# ST_SYS_Board_FPGA_SUP.net
KiCad netlist of a schematic drawn in Altium Designer
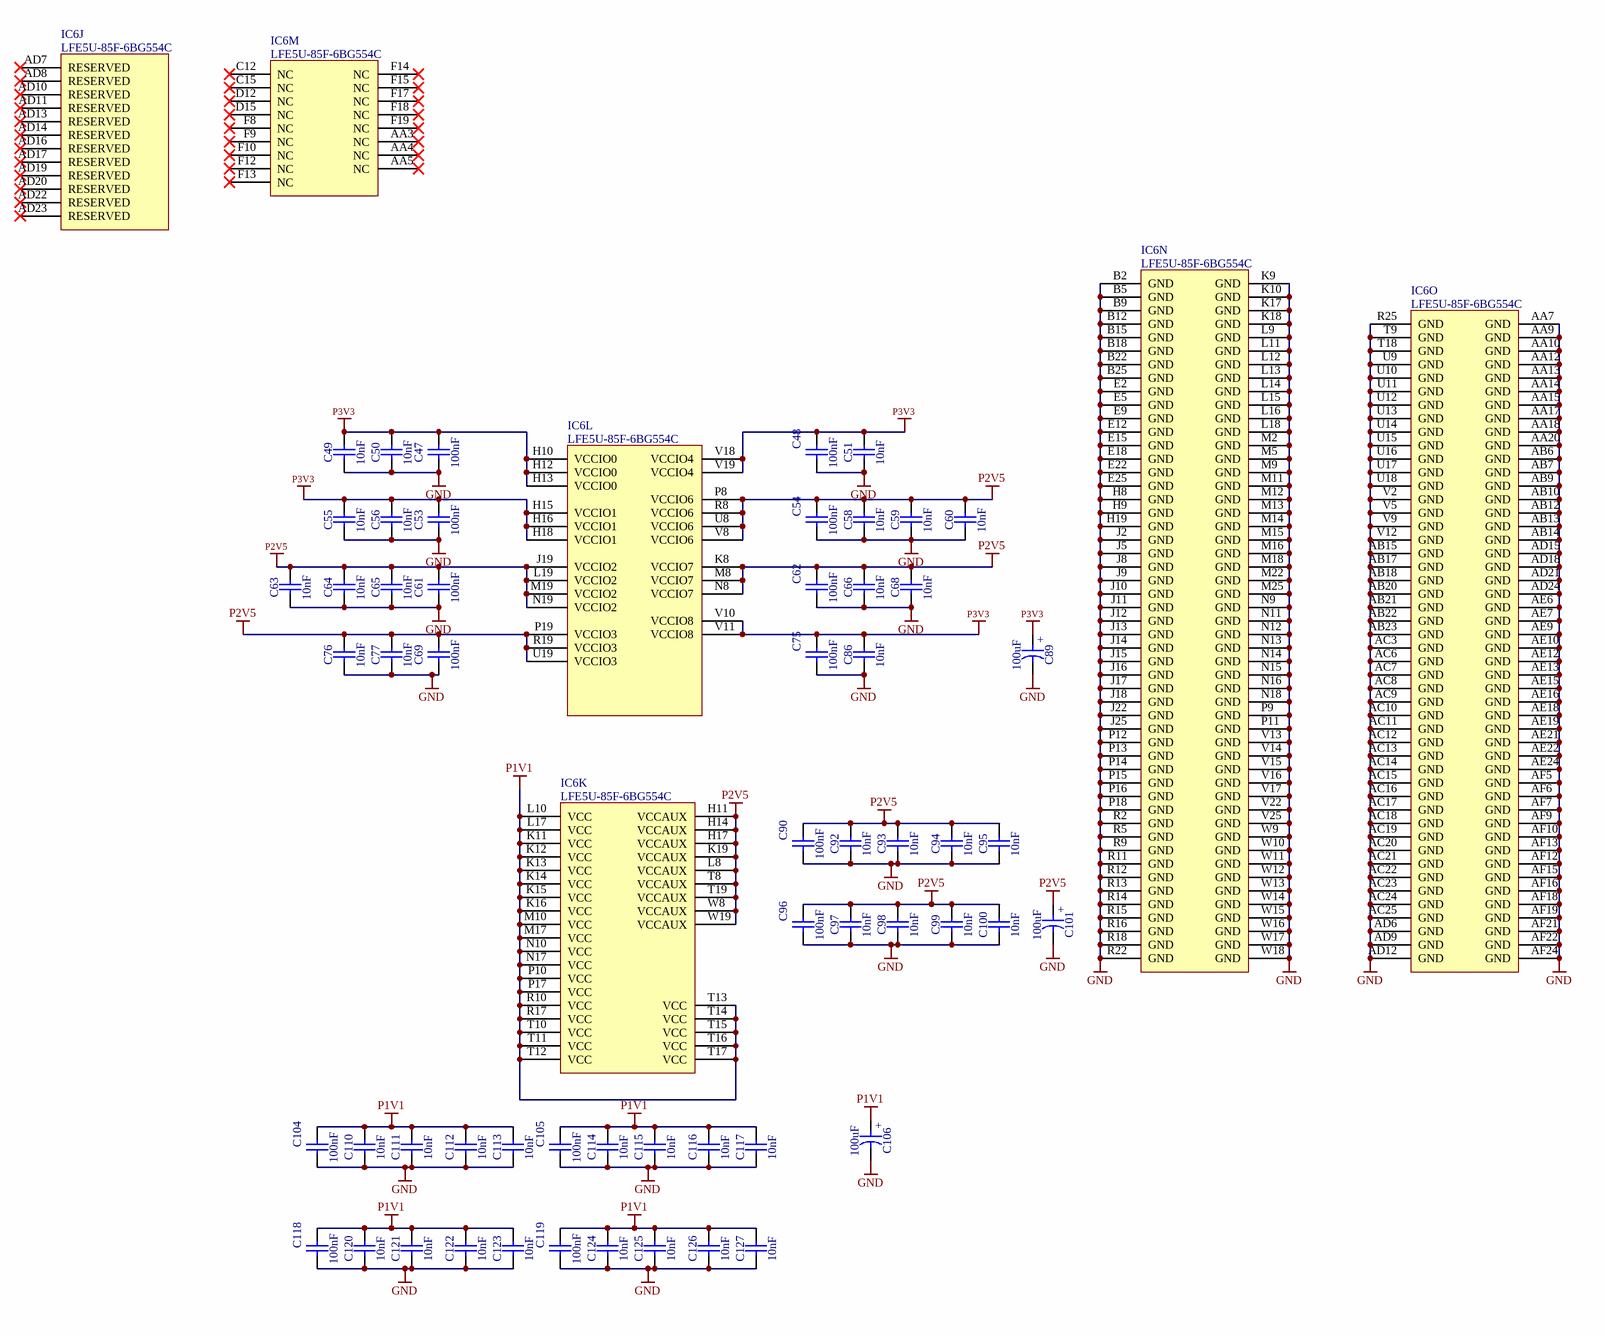
[diagram p0: ST_SYS_Board_FPGA_SUP.schdoc]

(export (version "E")
  (design (tool "Eeschema 10.0.6"))
  (components
    (comp (ref "C47")
      (value "100nF")
      (footprint "CAPC1005X55N")
      (description "Non-polarised capacitor")
      (fields
        (field (name "PART NUMBER") "CC0402_100NF_16V_10%_X5R")
        (field (name "VOLTAGE") "16V")
        (field (name "AUTHOR") "CERN DEM JLC")
      )
      (libsource (lib "Capacitors") (part "Capacitor - non polarized"))
    )
    (comp (ref "C48")
      (value "100nF")
      (footprint "CAPC1005X55N")
      (description "Non-polarised capacitor")
      (fields
        (field (name "PART NUMBER") "CC0402_100NF_16V_10%_X5R")
        (field (name "VOLTAGE") "16V")
        (field (name "AUTHOR") "CERN DEM JLC")
      )
      (libsource (lib "Capacitors") (part "Capacitor - non polarized"))
    )
    (comp (ref "C49")
      (value "10nF")
      (footprint "CAPC0603X33N")
      (description "Non-polarised capacitor")
      (fields
        (field (name "PART NUMBER") "CC0201_10NF_10V_10%_X5R")
        (field (name "VOLTAGE") "10V")
        (field (name "AUTHOR") "CERN DEM JLC")
      )
      (libsource (lib "Capacitors") (part "Capacitor - non polarized"))
    )
    (comp (ref "C50")
      (value "10nF")
      (footprint "CAPC0603X33N")
      (description "Non-polarised capacitor")
      (fields
        (field (name "PART NUMBER") "CC0201_10NF_10V_10%_X5R")
        (field (name "VOLTAGE") "10V")
        (field (name "AUTHOR") "CERN DEM JLC")
      )
      (libsource (lib "Capacitors") (part "Capacitor - non polarized"))
    )
    (comp (ref "C51")
      (value "10nF")
      (footprint "CAPC0603X33N")
      (description "Non-polarised capacitor")
      (fields
        (field (name "PART NUMBER") "CC0201_10NF_10V_10%_X5R")
        (field (name "VOLTAGE") "10V")
        (field (name "AUTHOR") "CERN DEM JLC")
      )
      (libsource (lib "Capacitors") (part "Capacitor - non polarized"))
    )
    (comp (ref "C53")
      (value "100nF")
      (footprint "CAPC1005X55N")
      (description "Non-polarised capacitor")
      (fields
        (field (name "PART NUMBER") "CC0402_100NF_16V_10%_X5R")
        (field (name "VOLTAGE") "16V")
        (field (name "AUTHOR") "CERN DEM JLC")
      )
      (libsource (lib "Capacitors") (part "Capacitor - non polarized"))
    )
    (comp (ref "C54")
      (value "100nF")
      (footprint "CAPC1005X55N")
      (description "Non-polarised capacitor")
      (fields
        (field (name "PART NUMBER") "CC0402_100NF_16V_10%_X5R")
        (field (name "VOLTAGE") "16V")
        (field (name "AUTHOR") "CERN DEM JLC")
      )
      (libsource (lib "Capacitors") (part "Capacitor - non polarized"))
    )
    (comp (ref "C55")
      (value "10nF")
      (footprint "CAPC0603X33N")
      (description "Non-polarised capacitor")
      (fields
        (field (name "PART NUMBER") "CC0201_10NF_10V_10%_X5R")
        (field (name "VOLTAGE") "10V")
        (field (name "AUTHOR") "CERN DEM JLC")
      )
      (libsource (lib "Capacitors") (part "Capacitor - non polarized"))
    )
    (comp (ref "C56")
      (value "10nF")
      (footprint "CAPC0603X33N")
      (description "Non-polarised capacitor")
      (fields
        (field (name "PART NUMBER") "CC0201_10NF_10V_10%_X5R")
        (field (name "VOLTAGE") "10V")
        (field (name "AUTHOR") "CERN DEM JLC")
      )
      (libsource (lib "Capacitors") (part "Capacitor - non polarized"))
    )
    (comp (ref "C58")
      (value "10nF")
      (footprint "CAPC0603X33N")
      (description "Non-polarised capacitor")
      (fields
        (field (name "PART NUMBER") "CC0201_10NF_10V_10%_X5R")
        (field (name "VOLTAGE") "10V")
        (field (name "AUTHOR") "CERN DEM JLC")
      )
      (libsource (lib "Capacitors") (part "Capacitor - non polarized"))
    )
    (comp (ref "C59")
      (value "10nF")
      (footprint "CAPC0603X33N")
      (description "Non-polarised capacitor")
      (fields
        (field (name "PART NUMBER") "CC0201_10NF_10V_10%_X5R")
        (field (name "VOLTAGE") "10V")
        (field (name "AUTHOR") "CERN DEM JLC")
      )
      (libsource (lib "Capacitors") (part "Capacitor - non polarized"))
    )
    (comp (ref "C60")
      (value "10nF")
      (footprint "CAPC0603X33N")
      (description "Non-polarised capacitor")
      (fields
        (field (name "PART NUMBER") "CC0201_10NF_10V_10%_X5R")
        (field (name "VOLTAGE") "10V")
        (field (name "AUTHOR") "CERN DEM JLC")
      )
      (libsource (lib "Capacitors") (part "Capacitor - non polarized"))
    )
    (comp (ref "C61")
      (value "100nF")
      (footprint "CAPC1005X55N")
      (description "Non-polarised capacitor")
      (fields
        (field (name "PART NUMBER") "CC0402_100NF_16V_10%_X5R")
        (field (name "VOLTAGE") "16V")
        (field (name "AUTHOR") "CERN DEM JLC")
      )
      (libsource (lib "Capacitors") (part "Capacitor - non polarized"))
    )
    (comp (ref "C62")
      (value "100nF")
      (footprint "CAPC1005X55N")
      (description "Non-polarised capacitor")
      (fields
        (field (name "PART NUMBER") "CC0402_100NF_16V_10%_X5R")
        (field (name "VOLTAGE") "16V")
        (field (name "AUTHOR") "CERN DEM JLC")
      )
      (libsource (lib "Capacitors") (part "Capacitor - non polarized"))
    )
    (comp (ref "C63")
      (value "10nF")
      (footprint "CAPC0603X33N")
      (description "Non-polarised capacitor")
      (fields
        (field (name "PART NUMBER") "CC0201_10NF_10V_10%_X5R")
        (field (name "VOLTAGE") "10V")
        (field (name "AUTHOR") "CERN DEM JLC")
      )
      (libsource (lib "Capacitors") (part "Capacitor - non polarized"))
    )
    (comp (ref "C64")
      (value "10nF")
      (footprint "CAPC0603X33N")
      (description "Non-polarised capacitor")
      (fields
        (field (name "PART NUMBER") "CC0201_10NF_10V_10%_X5R")
        (field (name "VOLTAGE") "10V")
        (field (name "AUTHOR") "CERN DEM JLC")
      )
      (libsource (lib "Capacitors") (part "Capacitor - non polarized"))
    )
    (comp (ref "C65")
      (value "10nF")
      (footprint "CAPC0603X33N")
      (description "Non-polarised capacitor")
      (fields
        (field (name "PART NUMBER") "CC0201_10NF_10V_10%_X5R")
        (field (name "VOLTAGE") "10V")
        (field (name "AUTHOR") "CERN DEM JLC")
      )
      (libsource (lib "Capacitors") (part "Capacitor - non polarized"))
    )
    (comp (ref "C66")
      (value "10nF")
      (footprint "CAPC0603X33N")
      (description "Non-polarised capacitor")
      (fields
        (field (name "PART NUMBER") "CC0201_10NF_10V_10%_X5R")
        (field (name "VOLTAGE") "10V")
        (field (name "AUTHOR") "CERN DEM JLC")
      )
      (libsource (lib "Capacitors") (part "Capacitor - non polarized"))
    )
    (comp (ref "C68")
      (value "10nF")
      (footprint "CAPC0603X33N")
      (description "Non-polarised capacitor")
      (fields
        (field (name "PART NUMBER") "CC0201_10NF_10V_10%_X5R")
        (field (name "VOLTAGE") "10V")
        (field (name "AUTHOR") "CERN DEM JLC")
      )
      (libsource (lib "Capacitors") (part "Capacitor - non polarized"))
    )
    (comp (ref "C69")
      (value "100nF")
      (footprint "CAPC1005X55N")
      (description "Non-polarised capacitor")
      (fields
        (field (name "PART NUMBER") "CC0402_100NF_16V_10%_X5R")
        (field (name "VOLTAGE") "16V")
        (field (name "AUTHOR") "CERN DEM JLC")
      )
      (libsource (lib "Capacitors") (part "Capacitor - non polarized"))
    )
    (comp (ref "C75")
      (value "100nF")
      (footprint "CAPC1005X55N")
      (description "Non-polarised capacitor")
      (fields
        (field (name "PART NUMBER") "CC0402_100NF_16V_10%_X5R")
        (field (name "VOLTAGE") "16V")
        (field (name "AUTHOR") "CERN DEM JLC")
      )
      (libsource (lib "Capacitors") (part "Capacitor - non polarized"))
    )
    (comp (ref "C76")
      (value "10nF")
      (footprint "CAPC0603X33N")
      (description "Non-polarised capacitor")
      (fields
        (field (name "PART NUMBER") "CC0201_10NF_10V_10%_X5R")
        (field (name "VOLTAGE") "10V")
        (field (name "AUTHOR") "CERN DEM JLC")
      )
      (libsource (lib "Capacitors") (part "Capacitor - non polarized"))
    )
    (comp (ref "C77")
      (value "10nF")
      (footprint "CAPC0603X33N")
      (description "Non-polarised capacitor")
      (fields
        (field (name "PART NUMBER") "CC0201_10NF_10V_10%_X5R")
        (field (name "VOLTAGE") "10V")
        (field (name "AUTHOR") "CERN DEM JLC")
      )
      (libsource (lib "Capacitors") (part "Capacitor - non polarized"))
    )
    (comp (ref "C86")
      (value "10nF")
      (footprint "CAPC0603X33N")
      (description "Non-polarised capacitor")
      (fields
        (field (name "PART NUMBER") "CC0201_10NF_10V_10%_X5R")
        (field (name "VOLTAGE") "10V")
        (field (name "AUTHOR") "CERN DEM JLC")
      )
      (libsource (lib "Capacitors") (part "Capacitor - non polarized"))
    )
    (comp (ref "C89")
      (value "100uF")
      (footprint "CAPMP3528X210N")
      (description "Polarised capacitor")
      (fields
        (field (name "PART NUMBER") "CTE3528-21_100UF_6.3V_20%_LESR015_KEMET_T520")
        (field (name "VOLTAGE") "6.3V")
        (field (name "AUTHOR") "CERN DEM BC")
      )
      (libsource (lib "Capacitors") (part "Capacitor - polarized"))
    )
    (comp (ref "C90")
      (value "100nF")
      (footprint "CAPC1005X55N")
      (description "Non-polarised capacitor")
      (fields
        (field (name "PART NUMBER") "CC0402_100NF_16V_10%_X5R")
        (field (name "VOLTAGE") "16V")
        (field (name "AUTHOR") "CERN DEM JLC")
      )
      (libsource (lib "Capacitors") (part "Capacitor - non polarized"))
    )
    (comp (ref "C92")
      (value "10nF")
      (footprint "CAPC0603X33N")
      (description "Non-polarised capacitor")
      (fields
        (field (name "PART NUMBER") "CC0201_10NF_10V_10%_X5R")
        (field (name "VOLTAGE") "10V")
        (field (name "AUTHOR") "CERN DEM JLC")
      )
      (libsource (lib "Capacitors") (part "Capacitor - non polarized"))
    )
    (comp (ref "C93")
      (value "10nF")
      (footprint "CAPC0603X33N")
      (description "Non-polarised capacitor")
      (fields
        (field (name "PART NUMBER") "CC0201_10NF_10V_10%_X5R")
        (field (name "VOLTAGE") "10V")
        (field (name "AUTHOR") "CERN DEM JLC")
      )
      (libsource (lib "Capacitors") (part "Capacitor - non polarized"))
    )
    (comp (ref "C94")
      (value "10nF")
      (footprint "CAPC0603X33N")
      (description "Non-polarised capacitor")
      (fields
        (field (name "PART NUMBER") "CC0201_10NF_10V_10%_X5R")
        (field (name "VOLTAGE") "10V")
        (field (name "AUTHOR") "CERN DEM JLC")
      )
      (libsource (lib "Capacitors") (part "Capacitor - non polarized"))
    )
    (comp (ref "C95")
      (value "10nF")
      (footprint "CAPC0603X33N")
      (description "Non-polarised capacitor")
      (fields
        (field (name "PART NUMBER") "CC0201_10NF_10V_10%_X5R")
        (field (name "VOLTAGE") "10V")
        (field (name "AUTHOR") "CERN DEM JLC")
      )
      (libsource (lib "Capacitors") (part "Capacitor - non polarized"))
    )
    (comp (ref "C96")
      (value "100nF")
      (footprint "CAPC1005X55N")
      (description "Non-polarised capacitor")
      (fields
        (field (name "PART NUMBER") "CC0402_100NF_16V_10%_X5R")
        (field (name "VOLTAGE") "16V")
        (field (name "AUTHOR") "CERN DEM JLC")
      )
      (libsource (lib "Capacitors") (part "Capacitor - non polarized"))
    )
    (comp (ref "C97")
      (value "10nF")
      (footprint "CAPC0603X33N")
      (description "Non-polarised capacitor")
      (fields
        (field (name "PART NUMBER") "CC0201_10NF_10V_10%_X5R")
        (field (name "VOLTAGE") "10V")
        (field (name "AUTHOR") "CERN DEM JLC")
      )
      (libsource (lib "Capacitors") (part "Capacitor - non polarized"))
    )
    (comp (ref "C98")
      (value "10nF")
      (footprint "CAPC0603X33N")
      (description "Non-polarised capacitor")
      (fields
        (field (name "PART NUMBER") "CC0201_10NF_10V_10%_X5R")
        (field (name "VOLTAGE") "10V")
        (field (name "AUTHOR") "CERN DEM JLC")
      )
      (libsource (lib "Capacitors") (part "Capacitor - non polarized"))
    )
    (comp (ref "C99")
      (value "10nF")
      (footprint "CAPC0603X33N")
      (description "Non-polarised capacitor")
      (fields
        (field (name "PART NUMBER") "CC0201_10NF_10V_10%_X5R")
        (field (name "VOLTAGE") "10V")
        (field (name "AUTHOR") "CERN DEM JLC")
      )
      (libsource (lib "Capacitors") (part "Capacitor - non polarized"))
    )
    (comp (ref "C100")
      (value "10nF")
      (footprint "CAPC0603X33N")
      (description "Non-polarised capacitor")
      (fields
        (field (name "PART NUMBER") "CC0201_10NF_10V_10%_X5R")
        (field (name "VOLTAGE") "10V")
        (field (name "AUTHOR") "CERN DEM JLC")
      )
      (libsource (lib "Capacitors") (part "Capacitor - non polarized"))
    )
    (comp (ref "C101")
      (value "100uF")
      (footprint "CAPMP3528X210N")
      (description "Polarised capacitor")
      (fields
        (field (name "PART NUMBER") "CTE3528-21_100UF_6.3V_20%_LESR015_KEMET_T520")
        (field (name "VOLTAGE") "6.3V")
        (field (name "AUTHOR") "CERN DEM BC")
      )
      (libsource (lib "Capacitors") (part "Capacitor - polarized"))
    )
    (comp (ref "C104")
      (value "100nF")
      (footprint "CAPC1005X55N")
      (description "Non-polarised capacitor")
      (fields
        (field (name "PART NUMBER") "CC0402_100NF_16V_10%_X5R")
        (field (name "VOLTAGE") "16V")
        (field (name "AUTHOR") "CERN DEM JLC")
      )
      (libsource (lib "Capacitors") (part "Capacitor - non polarized"))
    )
    (comp (ref "C105")
      (value "100nF")
      (footprint "CAPC1005X55N")
      (description "Non-polarised capacitor")
      (fields
        (field (name "PART NUMBER") "CC0402_100NF_16V_10%_X5R")
        (field (name "VOLTAGE") "16V")
        (field (name "AUTHOR") "CERN DEM JLC")
      )
      (libsource (lib "Capacitors") (part "Capacitor - non polarized"))
    )
    (comp (ref "C106")
      (value "100uF")
      (footprint "CAPMP3528X210N")
      (description "Polarised capacitor")
      (fields
        (field (name "PART NUMBER") "CTE3528-21_100UF_6.3V_20%_LESR015_KEMET_T520")
        (field (name "VOLTAGE") "6.3V")
        (field (name "AUTHOR") "CERN DEM BC")
      )
      (libsource (lib "Capacitors") (part "Capacitor - polarized"))
    )
    (comp (ref "C110")
      (value "10nF")
      (footprint "CAPC0603X33N")
      (description "Non-polarised capacitor")
      (fields
        (field (name "PART NUMBER") "CC0201_10NF_10V_10%_X5R")
        (field (name "VOLTAGE") "10V")
        (field (name "AUTHOR") "CERN DEM JLC")
      )
      (libsource (lib "Capacitors") (part "Capacitor - non polarized"))
    )
    (comp (ref "C111")
      (value "10nF")
      (footprint "CAPC0603X33N")
      (description "Non-polarised capacitor")
      (fields
        (field (name "PART NUMBER") "CC0201_10NF_10V_10%_X5R")
        (field (name "VOLTAGE") "10V")
        (field (name "AUTHOR") "CERN DEM JLC")
      )
      (libsource (lib "Capacitors") (part "Capacitor - non polarized"))
    )
    (comp (ref "C112")
      (value "10nF")
      (footprint "CAPC0603X33N")
      (description "Non-polarised capacitor")
      (fields
        (field (name "PART NUMBER") "CC0201_10NF_10V_10%_X5R")
        (field (name "VOLTAGE") "10V")
        (field (name "AUTHOR") "CERN DEM JLC")
      )
      (libsource (lib "Capacitors") (part "Capacitor - non polarized"))
    )
    (comp (ref "C113")
      (value "10nF")
      (footprint "CAPC0603X33N")
      (description "Non-polarised capacitor")
      (fields
        (field (name "PART NUMBER") "CC0201_10NF_10V_10%_X5R")
        (field (name "VOLTAGE") "10V")
        (field (name "AUTHOR") "CERN DEM JLC")
      )
      (libsource (lib "Capacitors") (part "Capacitor - non polarized"))
    )
    (comp (ref "C114")
      (value "10nF")
      (footprint "CAPC0603X33N")
      (description "Non-polarised capacitor")
      (fields
        (field (name "PART NUMBER") "CC0201_10NF_10V_10%_X5R")
        (field (name "VOLTAGE") "10V")
        (field (name "AUTHOR") "CERN DEM JLC")
      )
      (libsource (lib "Capacitors") (part "Capacitor - non polarized"))
    )
    (comp (ref "C115")
      (value "10nF")
      (footprint "CAPC0603X33N")
      (description "Non-polarised capacitor")
      (fields
        (field (name "PART NUMBER") "CC0201_10NF_10V_10%_X5R")
        (field (name "VOLTAGE") "10V")
        (field (name "AUTHOR") "CERN DEM JLC")
      )
      (libsource (lib "Capacitors") (part "Capacitor - non polarized"))
    )
    (comp (ref "C116")
      (value "10nF")
      (footprint "CAPC0603X33N")
      (description "Non-polarised capacitor")
      (fields
        (field (name "PART NUMBER") "CC0201_10NF_10V_10%_X5R")
        (field (name "VOLTAGE") "10V")
        (field (name "AUTHOR") "CERN DEM JLC")
      )
      (libsource (lib "Capacitors") (part "Capacitor - non polarized"))
    )
    (comp (ref "C117")
      (value "10nF")
      (footprint "CAPC0603X33N")
      (description "Non-polarised capacitor")
      (fields
        (field (name "PART NUMBER") "CC0201_10NF_10V_10%_X5R")
        (field (name "VOLTAGE") "10V")
        (field (name "AUTHOR") "CERN DEM JLC")
      )
      (libsource (lib "Capacitors") (part "Capacitor - non polarized"))
    )
    (comp (ref "C118")
      (value "100nF")
      (footprint "CAPC1005X55N")
      (description "Non-polarised capacitor")
      (fields
        (field (name "PART NUMBER") "CC0402_100NF_16V_10%_X5R")
        (field (name "VOLTAGE") "16V")
        (field (name "AUTHOR") "CERN DEM JLC")
      )
      (libsource (lib "Capacitors") (part "Capacitor - non polarized"))
    )
    (comp (ref "C119")
      (value "100nF")
      (footprint "CAPC1005X55N")
      (description "Non-polarised capacitor")
      (fields
        (field (name "PART NUMBER") "CC0402_100NF_16V_10%_X5R")
        (field (name "VOLTAGE") "16V")
        (field (name "AUTHOR") "CERN DEM JLC")
      )
      (libsource (lib "Capacitors") (part "Capacitor - non polarized"))
    )
    (comp (ref "C120")
      (value "10nF")
      (footprint "CAPC0603X33N")
      (description "Non-polarised capacitor")
      (fields
        (field (name "PART NUMBER") "CC0201_10NF_10V_10%_X5R")
        (field (name "VOLTAGE") "10V")
        (field (name "AUTHOR") "CERN DEM JLC")
      )
      (libsource (lib "Capacitors") (part "Capacitor - non polarized"))
    )
    (comp (ref "C121")
      (value "10nF")
      (footprint "CAPC0603X33N")
      (description "Non-polarised capacitor")
      (fields
        (field (name "PART NUMBER") "CC0201_10NF_10V_10%_X5R")
        (field (name "VOLTAGE") "10V")
        (field (name "AUTHOR") "CERN DEM JLC")
      )
      (libsource (lib "Capacitors") (part "Capacitor - non polarized"))
    )
    (comp (ref "C122")
      (value "10nF")
      (footprint "CAPC0603X33N")
      (description "Non-polarised capacitor")
      (fields
        (field (name "PART NUMBER") "CC0201_10NF_10V_10%_X5R")
        (field (name "VOLTAGE") "10V")
        (field (name "AUTHOR") "CERN DEM JLC")
      )
      (libsource (lib "Capacitors") (part "Capacitor - non polarized"))
    )
    (comp (ref "C123")
      (value "10nF")
      (footprint "CAPC0603X33N")
      (description "Non-polarised capacitor")
      (fields
        (field (name "PART NUMBER") "CC0201_10NF_10V_10%_X5R")
        (field (name "VOLTAGE") "10V")
        (field (name "AUTHOR") "CERN DEM JLC")
      )
      (libsource (lib "Capacitors") (part "Capacitor - non polarized"))
    )
    (comp (ref "C124")
      (value "10nF")
      (footprint "CAPC0603X33N")
      (description "Non-polarised capacitor")
      (fields
        (field (name "PART NUMBER") "CC0201_10NF_10V_10%_X5R")
        (field (name "VOLTAGE") "10V")
        (field (name "AUTHOR") "CERN DEM JLC")
      )
      (libsource (lib "Capacitors") (part "Capacitor - non polarized"))
    )
    (comp (ref "C125")
      (value "10nF")
      (footprint "CAPC0603X33N")
      (description "Non-polarised capacitor")
      (fields
        (field (name "PART NUMBER") "CC0201_10NF_10V_10%_X5R")
        (field (name "VOLTAGE") "10V")
        (field (name "AUTHOR") "CERN DEM JLC")
      )
      (libsource (lib "Capacitors") (part "Capacitor - non polarized"))
    )
    (comp (ref "C126")
      (value "10nF")
      (footprint "CAPC0603X33N")
      (description "Non-polarised capacitor")
      (fields
        (field (name "PART NUMBER") "CC0201_10NF_10V_10%_X5R")
        (field (name "VOLTAGE") "10V")
        (field (name "AUTHOR") "CERN DEM JLC")
      )
      (libsource (lib "Capacitors") (part "Capacitor - non polarized"))
    )
    (comp (ref "C127")
      (value "10nF")
      (footprint "CAPC0603X33N")
      (description "Non-polarised capacitor")
      (fields
        (field (name "PART NUMBER") "CC0201_10NF_10V_10%_X5R")
        (field (name "VOLTAGE") "10V")
        (field (name "AUTHOR") "CERN DEM JLC")
      )
      (libsource (lib "Capacitors") (part "Capacitor - non polarized"))
    )
    (comp (ref "IC6")
      (value "LFE5U-85F-6BG554C")
      (footprint "BGA554C80P26X26_2300X2300X176")
      (fields (field (name "MANUFACTURER") "LATTICE SEMICONDUCTOR") (field (name "AUTHOR") "CERN DEM HF"))
      (libsource (lib "ICs And Semiconductors") (part "LFE5U-85F-6BG554C"))
    )
  )
  (nets
    (net (code "1") (name "GND") (class "Default")
      (node (ref "C100") (pin "1") (pinfunction "1_1") (pintype "passive"))
      (node (ref "C101") (pin "2") (pinfunction "2_2") (pintype "passive"))
      (node (ref "C104") (pin "1") (pinfunction "1_1") (pintype "passive"))
      (node (ref "C105") (pin "1") (pinfunction "1_1") (pintype "passive"))
      (node (ref "C106") (pin "2") (pinfunction "2_2") (pintype "passive"))
      (node (ref "C110") (pin "1") (pinfunction "1_1") (pintype "passive"))
      (node (ref "C111") (pin "1") (pinfunction "1_1") (pintype "passive"))
      (node (ref "C112") (pin "1") (pinfunction "1_1") (pintype "passive"))
      (node (ref "C113") (pin "1") (pinfunction "1_1") (pintype "passive"))
      (node (ref "C114") (pin "1") (pinfunction "1_1") (pintype "passive"))
      (node (ref "C115") (pin "1") (pinfunction "1_1") (pintype "passive"))
      (node (ref "C116") (pin "1") (pinfunction "1_1") (pintype "passive"))
      (node (ref "C117") (pin "1") (pinfunction "1_1") (pintype "passive"))
      (node (ref "C118") (pin "1") (pinfunction "1_1") (pintype "passive"))
      (node (ref "C119") (pin "1") (pinfunction "1_1") (pintype "passive"))
      (node (ref "C120") (pin "1") (pinfunction "1_1") (pintype "passive"))
      (node (ref "C121") (pin "1") (pinfunction "1_1") (pintype "passive"))
      (node (ref "C122") (pin "1") (pinfunction "1_1") (pintype "passive"))
      (node (ref "C123") (pin "1") (pinfunction "1_1") (pintype "passive"))
      (node (ref "C124") (pin "1") (pinfunction "1_1") (pintype "passive"))
      (node (ref "C125") (pin "1") (pinfunction "1_1") (pintype "passive"))
      (node (ref "C126") (pin "1") (pinfunction "1_1") (pintype "passive"))
      (node (ref "C127") (pin "1") (pinfunction "1_1") (pintype "passive"))
      (node (ref "C47") (pin "1") (pinfunction "1_1") (pintype "passive"))
      (node (ref "C48") (pin "1") (pinfunction "1_1") (pintype "passive"))
      (node (ref "C49") (pin "1") (pinfunction "1_1") (pintype "passive"))
      (node (ref "C50") (pin "1") (pinfunction "1_1") (pintype "passive"))
      (node (ref "C51") (pin "1") (pinfunction "1_1") (pintype "passive"))
      (node (ref "C53") (pin "1") (pinfunction "1_1") (pintype "passive"))
      (node (ref "C54") (pin "1") (pinfunction "1_1") (pintype "passive"))
      (node (ref "C55") (pin "1") (pinfunction "1_1") (pintype "passive"))
      (node (ref "C56") (pin "1") (pinfunction "1_1") (pintype "passive"))
      (node (ref "C58") (pin "1") (pinfunction "1_1") (pintype "passive"))
      (node (ref "C59") (pin "1") (pinfunction "1_1") (pintype "passive"))
      (node (ref "C60") (pin "1") (pinfunction "1_1") (pintype "passive"))
      (node (ref "C61") (pin "1") (pinfunction "1_1") (pintype "passive"))
      (node (ref "C62") (pin "1") (pinfunction "1_1") (pintype "passive"))
      (node (ref "C63") (pin "1") (pinfunction "1_1") (pintype "passive"))
      (node (ref "C64") (pin "1") (pinfunction "1_1") (pintype "passive"))
      (node (ref "C65") (pin "1") (pinfunction "1_1") (pintype "passive"))
      (node (ref "C66") (pin "1") (pinfunction "1_1") (pintype "passive"))
      (node (ref "C68") (pin "1") (pinfunction "1_1") (pintype "passive"))
      (node (ref "C69") (pin "1") (pinfunction "1_1") (pintype "passive"))
      (node (ref "C75") (pin "1") (pinfunction "1_1") (pintype "passive"))
      (node (ref "C76") (pin "1") (pinfunction "1_1") (pintype "passive"))
      (node (ref "C77") (pin "1") (pinfunction "1_1") (pintype "passive"))
      (node (ref "C86") (pin "1") (pinfunction "1_1") (pintype "passive"))
      (node (ref "C89") (pin "2") (pinfunction "2_2") (pintype "passive"))
      (node (ref "C90") (pin "1") (pinfunction "1_1") (pintype "passive"))
      (node (ref "C92") (pin "1") (pinfunction "1_1") (pintype "passive"))
      (node (ref "C93") (pin "1") (pinfunction "1_1") (pintype "passive"))
      (node (ref "C94") (pin "1") (pinfunction "1_1") (pintype "passive"))
      (node (ref "C95") (pin "1") (pinfunction "1_1") (pintype "passive"))
      (node (ref "C96") (pin "1") (pinfunction "1_1") (pintype "passive"))
      (node (ref "C97") (pin "1") (pinfunction "1_1") (pintype "passive"))
      (node (ref "C98") (pin "1") (pinfunction "1_1") (pintype "passive"))
      (node (ref "C99") (pin "1") (pinfunction "1_1") (pintype "passive"))
      (node (ref "IC6") (pin "AA10") (pinfunction "GND_AA10") (pintype "power_in"))
      (node (ref "IC6") (pin "AA12") (pinfunction "GND_AA12") (pintype "power_in"))
      (node (ref "IC6") (pin "AA13") (pinfunction "GND_AA13") (pintype "power_in"))
      (node (ref "IC6") (pin "AA14") (pinfunction "GND_AA14") (pintype "power_in"))
      (node (ref "IC6") (pin "AA15") (pinfunction "GND_AA15") (pintype "power_in"))
      (node (ref "IC6") (pin "AA17") (pinfunction "GND_AA17") (pintype "power_in"))
      (node (ref "IC6") (pin "AA18") (pinfunction "GND_AA18") (pintype "power_in"))
      (node (ref "IC6") (pin "AA20") (pinfunction "GND_AA20") (pintype "power_in"))
      (node (ref "IC6") (pin "AA7") (pinfunction "GND_AA7") (pintype "power_in"))
      (node (ref "IC6") (pin "AA9") (pinfunction "GND_AA9") (pintype "power_in"))
      (node (ref "IC6") (pin "AB10") (pinfunction "GND_AB10") (pintype "power_in"))
      (node (ref "IC6") (pin "AB12") (pinfunction "GND_AB12") (pintype "power_in"))
      (node (ref "IC6") (pin "AB13") (pinfunction "GND_AB13") (pintype "power_in"))
      (node (ref "IC6") (pin "AB14") (pinfunction "GND_AB14") (pintype "power_in"))
      (node (ref "IC6") (pin "AB15") (pinfunction "GND_AB15") (pintype "power_in"))
      (node (ref "IC6") (pin "AB17") (pinfunction "GND_AB17") (pintype "power_in"))
      (node (ref "IC6") (pin "AB18") (pinfunction "GND_AB18") (pintype "power_in"))
      (node (ref "IC6") (pin "AB20") (pinfunction "GND_AB20") (pintype "power_in"))
      (node (ref "IC6") (pin "AB21") (pinfunction "GND_AB21") (pintype "power_in"))
      (node (ref "IC6") (pin "AB22") (pinfunction "GND_AB22") (pintype "power_in"))
      (node (ref "IC6") (pin "AB23") (pinfunction "GND_AB23") (pintype "power_in"))
      (node (ref "IC6") (pin "AB6") (pinfunction "GND_AB6") (pintype "power_in"))
      (node (ref "IC6") (pin "AB7") (pinfunction "GND_AB7") (pintype "power_in"))
      (node (ref "IC6") (pin "AB9") (pinfunction "GND_AB9") (pintype "power_in"))
      (node (ref "IC6") (pin "AC10") (pinfunction "GND_AC10") (pintype "power_in"))
      (node (ref "IC6") (pin "AC11") (pinfunction "GND_AC11") (pintype "power_in"))
      (node (ref "IC6") (pin "AC12") (pinfunction "GND_AC12") (pintype "power_in"))
      (node (ref "IC6") (pin "AC13") (pinfunction "GND_AC13") (pintype "power_in"))
      (node (ref "IC6") (pin "AC14") (pinfunction "GND_AC14") (pintype "power_in"))
      (node (ref "IC6") (pin "AC15") (pinfunction "GND_AC15") (pintype "power_in"))
      (node (ref "IC6") (pin "AC16") (pinfunction "GND_AC16") (pintype "power_in"))
      (node (ref "IC6") (pin "AC17") (pinfunction "GND_AC17") (pintype "power_in"))
      (node (ref "IC6") (pin "AC18") (pinfunction "GND_AC18") (pintype "power_in"))
      (node (ref "IC6") (pin "AC19") (pinfunction "GND_AC19") (pintype "power_in"))
      (node (ref "IC6") (pin "AC20") (pinfunction "GND_AC20") (pintype "power_in"))
      (node (ref "IC6") (pin "AC21") (pinfunction "GND_AC21") (pintype "power_in"))
      (node (ref "IC6") (pin "AC22") (pinfunction "GND_AC22") (pintype "power_in"))
      (node (ref "IC6") (pin "AC23") (pinfunction "GND_AC23") (pintype "power_in"))
      (node (ref "IC6") (pin "AC24") (pinfunction "GND_AC24") (pintype "power_in"))
      (node (ref "IC6") (pin "AC25") (pinfunction "GND_AC25") (pintype "power_in"))
      (node (ref "IC6") (pin "AC3") (pinfunction "GND_AC3") (pintype "power_in"))
      (node (ref "IC6") (pin "AC6") (pinfunction "GND_AC6") (pintype "power_in"))
      (node (ref "IC6") (pin "AC7") (pinfunction "GND_AC7") (pintype "power_in"))
      (node (ref "IC6") (pin "AC8") (pinfunction "GND_AC8") (pintype "power_in"))
      (node (ref "IC6") (pin "AC9") (pinfunction "GND_AC9") (pintype "power_in"))
      (node (ref "IC6") (pin "AD12") (pinfunction "GND_AD12") (pintype "power_in"))
      (node (ref "IC6") (pin "AD15") (pinfunction "GND_AD15") (pintype "power_in"))
      (node (ref "IC6") (pin "AD18") (pinfunction "GND_AD18") (pintype "power_in"))
      (node (ref "IC6") (pin "AD21") (pinfunction "GND_AD21") (pintype "power_in"))
      (node (ref "IC6") (pin "AD24") (pinfunction "GND_AD24") (pintype "power_in"))
      (node (ref "IC6") (pin "AD6") (pinfunction "GND_AD6") (pintype "power_in"))
      (node (ref "IC6") (pin "AD9") (pinfunction "GND_AD9") (pintype "power_in"))
      (node (ref "IC6") (pin "AE10") (pinfunction "GND_AE10") (pintype "power_in"))
      (node (ref "IC6") (pin "AE12") (pinfunction "GND_AE12") (pintype "power_in"))
      (node (ref "IC6") (pin "AE13") (pinfunction "GND_AE13") (pintype "power_in"))
      (node (ref "IC6") (pin "AE15") (pinfunction "GND_AE15") (pintype "power_in"))
      (node (ref "IC6") (pin "AE16") (pinfunction "GND_AE16") (pintype "power_in"))
      (node (ref "IC6") (pin "AE18") (pinfunction "GND_AE18") (pintype "power_in"))
      (node (ref "IC6") (pin "AE19") (pinfunction "GND_AE19") (pintype "power_in"))
      (node (ref "IC6") (pin "AE21") (pinfunction "GND_AE21") (pintype "power_in"))
      (node (ref "IC6") (pin "AE22") (pinfunction "GND_AE22") (pintype "power_in"))
      (node (ref "IC6") (pin "AE24") (pinfunction "GND_AE24") (pintype "power_in"))
      (node (ref "IC6") (pin "AE6") (pinfunction "GND_AE6") (pintype "power_in"))
      (node (ref "IC6") (pin "AE7") (pinfunction "GND_AE7") (pintype "power_in"))
      (node (ref "IC6") (pin "AE9") (pinfunction "GND_AE9") (pintype "power_in"))
      (node (ref "IC6") (pin "AF10") (pinfunction "GND_AF10") (pintype "power_in"))
      (node (ref "IC6") (pin "AF12") (pinfunction "GND_AF12") (pintype "power_in"))
      (node (ref "IC6") (pin "AF13") (pinfunction "GND_AF13") (pintype "power_in"))
      (node (ref "IC6") (pin "AF15") (pinfunction "GND_AF15") (pintype "power_in"))
      (node (ref "IC6") (pin "AF16") (pinfunction "GND_AF16") (pintype "power_in"))
      (node (ref "IC6") (pin "AF18") (pinfunction "GND_AF18") (pintype "power_in"))
      (node (ref "IC6") (pin "AF19") (pinfunction "GND_AF19") (pintype "power_in"))
      (node (ref "IC6") (pin "AF21") (pinfunction "GND_AF21") (pintype "power_in"))
      (node (ref "IC6") (pin "AF22") (pinfunction "GND_AF22") (pintype "power_in"))
      (node (ref "IC6") (pin "AF24") (pinfunction "GND_AF24") (pintype "power_in"))
      (node (ref "IC6") (pin "AF5") (pinfunction "GND_AF5") (pintype "power_in"))
      (node (ref "IC6") (pin "AF6") (pinfunction "GND_AF6") (pintype "power_in"))
      (node (ref "IC6") (pin "AF7") (pinfunction "GND_AF7") (pintype "power_in"))
      (node (ref "IC6") (pin "AF9") (pinfunction "GND_AF9") (pintype "power_in"))
      (node (ref "IC6") (pin "B12") (pinfunction "GND_B12") (pintype "power_in"))
      (node (ref "IC6") (pin "B15") (pinfunction "GND_B15") (pintype "power_in"))
      (node (ref "IC6") (pin "B18") (pinfunction "GND_B18") (pintype "power_in"))
      (node (ref "IC6") (pin "B2") (pinfunction "GND_B2") (pintype "power_in"))
      (node (ref "IC6") (pin "B22") (pinfunction "GND_B22") (pintype "power_in"))
      (node (ref "IC6") (pin "B25") (pinfunction "GND_B25") (pintype "power_in"))
      (node (ref "IC6") (pin "B5") (pinfunction "GND_B5") (pintype "power_in"))
      (node (ref "IC6") (pin "B9") (pinfunction "GND_B9") (pintype "power_in"))
      (node (ref "IC6") (pin "E12") (pinfunction "GND_E12") (pintype "power_in"))
      (node (ref "IC6") (pin "E15") (pinfunction "GND_E15") (pintype "power_in"))
      (node (ref "IC6") (pin "E18") (pinfunction "GND_E18") (pintype "power_in"))
      (node (ref "IC6") (pin "E2") (pinfunction "GND_E2") (pintype "power_in"))
      (node (ref "IC6") (pin "E22") (pinfunction "GND_E22") (pintype "power_in"))
      (node (ref "IC6") (pin "E25") (pinfunction "GND_E25") (pintype "power_in"))
      (node (ref "IC6") (pin "E5") (pinfunction "GND_E5") (pintype "power_in"))
      (node (ref "IC6") (pin "E9") (pinfunction "GND_E9") (pintype "power_in"))
      (node (ref "IC6") (pin "H19") (pinfunction "GND_H19") (pintype "power_in"))
      (node (ref "IC6") (pin "H8") (pinfunction "GND_H8") (pintype "power_in"))
      (node (ref "IC6") (pin "H9") (pinfunction "GND_H9") (pintype "power_in"))
      (node (ref "IC6") (pin "J10") (pinfunction "GND_J10") (pintype "power_in"))
      (node (ref "IC6") (pin "J11") (pinfunction "GND_J11") (pintype "power_in"))
      (node (ref "IC6") (pin "J12") (pinfunction "GND_J12") (pintype "power_in"))
      (node (ref "IC6") (pin "J13") (pinfunction "GND_J13") (pintype "power_in"))
      (node (ref "IC6") (pin "J14") (pinfunction "GND_J14") (pintype "power_in"))
      (node (ref "IC6") (pin "J15") (pinfunction "GND_J15") (pintype "power_in"))
      (node (ref "IC6") (pin "J16") (pinfunction "GND_J16") (pintype "power_in"))
      (node (ref "IC6") (pin "J17") (pinfunction "GND_J17") (pintype "power_in"))
      (node (ref "IC6") (pin "J18") (pinfunction "GND_J18") (pintype "power_in"))
      (node (ref "IC6") (pin "J2") (pinfunction "GND_J2") (pintype "power_in"))
      (node (ref "IC6") (pin "J22") (pinfunction "GND_J22") (pintype "power_in"))
      (node (ref "IC6") (pin "J25") (pinfunction "GND_J25") (pintype "power_in"))
      (node (ref "IC6") (pin "J5") (pinfunction "GND_J5") (pintype "power_in"))
      (node (ref "IC6") (pin "J8") (pinfunction "GND_J8") (pintype "power_in"))
      (node (ref "IC6") (pin "J9") (pinfunction "GND_J9") (pintype "power_in"))
      (node (ref "IC6") (pin "K10") (pinfunction "GND_K10") (pintype "power_in"))
      (node (ref "IC6") (pin "K17") (pinfunction "GND_K17") (pintype "power_in"))
      (node (ref "IC6") (pin "K18") (pinfunction "GND_K18") (pintype "power_in"))
      (node (ref "IC6") (pin "K9") (pinfunction "GND_K9") (pintype "power_in"))
      (node (ref "IC6") (pin "L11") (pinfunction "GND_L11") (pintype "power_in"))
      (node (ref "IC6") (pin "L12") (pinfunction "GND_L12") (pintype "power_in"))
      (node (ref "IC6") (pin "L13") (pinfunction "GND_L13") (pintype "power_in"))
      (node (ref "IC6") (pin "L14") (pinfunction "GND_L14") (pintype "power_in"))
      (node (ref "IC6") (pin "L15") (pinfunction "GND_L15") (pintype "power_in"))
      (node (ref "IC6") (pin "L16") (pinfunction "GND_L16") (pintype "power_in"))
      (node (ref "IC6") (pin "L18") (pinfunction "GND_L18") (pintype "power_in"))
      (node (ref "IC6") (pin "L9") (pinfunction "GND_L9") (pintype "power_in"))
      (node (ref "IC6") (pin "M11") (pinfunction "GND_M11") (pintype "power_in"))
      (node (ref "IC6") (pin "M12") (pinfunction "GND_M12") (pintype "power_in"))
      (node (ref "IC6") (pin "M13") (pinfunction "GND_M13") (pintype "power_in"))
      (node (ref "IC6") (pin "M14") (pinfunction "GND_M14") (pintype "power_in"))
      (node (ref "IC6") (pin "M15") (pinfunction "GND_M15") (pintype "power_in"))
      (node (ref "IC6") (pin "M16") (pinfunction "GND_M16") (pintype "power_in"))
      (node (ref "IC6") (pin "M18") (pinfunction "GND_M18") (pintype "power_in"))
      (node (ref "IC6") (pin "M2") (pinfunction "GND_M2") (pintype "power_in"))
      (node (ref "IC6") (pin "M22") (pinfunction "GND_M22") (pintype "power_in"))
      (node (ref "IC6") (pin "M25") (pinfunction "GND_M25") (pintype "power_in"))
      (node (ref "IC6") (pin "M5") (pinfunction "GND_M5") (pintype "power_in"))
      (node (ref "IC6") (pin "M9") (pinfunction "GND_M9") (pintype "power_in"))
      (node (ref "IC6") (pin "N11") (pinfunction "GND_N11") (pintype "power_in"))
      (node (ref "IC6") (pin "N12") (pinfunction "GND_N12") (pintype "power_in"))
      (node (ref "IC6") (pin "N13") (pinfunction "GND_N13") (pintype "power_in"))
      (node (ref "IC6") (pin "N14") (pinfunction "GND_N14") (pintype "power_in"))
      (node (ref "IC6") (pin "N15") (pinfunction "GND_N15") (pintype "power_in"))
      (node (ref "IC6") (pin "N16") (pinfunction "GND_N16") (pintype "power_in"))
      (node (ref "IC6") (pin "N18") (pinfunction "GND_N18") (pintype "power_in"))
      (node (ref "IC6") (pin "N9") (pinfunction "GND_N9") (pintype "power_in"))
      (node (ref "IC6") (pin "P11") (pinfunction "GND_P11") (pintype "power_in"))
      (node (ref "IC6") (pin "P12") (pinfunction "GND_P12") (pintype "power_in"))
      (node (ref "IC6") (pin "P13") (pinfunction "GND_P13") (pintype "power_in"))
      (node (ref "IC6") (pin "P14") (pinfunction "GND_P14") (pintype "power_in"))
      (node (ref "IC6") (pin "P15") (pinfunction "GND_P15") (pintype "power_in"))
      (node (ref "IC6") (pin "P16") (pinfunction "GND_P16") (pintype "power_in"))
      (node (ref "IC6") (pin "P18") (pinfunction "GND_P18") (pintype "power_in"))
      (node (ref "IC6") (pin "P9") (pinfunction "GND_P9") (pintype "power_in"))
      (node (ref "IC6") (pin "R11") (pinfunction "GND_R11") (pintype "power_in"))
      (node (ref "IC6") (pin "R12") (pinfunction "GND_R12") (pintype "power_in"))
      (node (ref "IC6") (pin "R13") (pinfunction "GND_R13") (pintype "power_in"))
      (node (ref "IC6") (pin "R14") (pinfunction "GND_R14") (pintype "power_in"))
      (node (ref "IC6") (pin "R15") (pinfunction "GND_R15") (pintype "power_in"))
      (node (ref "IC6") (pin "R16") (pinfunction "GND_R16") (pintype "power_in"))
      (node (ref "IC6") (pin "R18") (pinfunction "GND_R18") (pintype "power_in"))
      (node (ref "IC6") (pin "R2") (pinfunction "GND_R2") (pintype "power_in"))
      (node (ref "IC6") (pin "R22") (pinfunction "GND_R22") (pintype "power_in"))
      (node (ref "IC6") (pin "R25") (pinfunction "GND_R25") (pintype "power_in"))
      (node (ref "IC6") (pin "R5") (pinfunction "GND_R5") (pintype "power_in"))
      (node (ref "IC6") (pin "R9") (pinfunction "GND_R9") (pintype "power_in"))
      (node (ref "IC6") (pin "T18") (pinfunction "GND_T18") (pintype "power_in"))
      (node (ref "IC6") (pin "T9") (pinfunction "GND_T9") (pintype "power_in"))
      (node (ref "IC6") (pin "U10") (pinfunction "GND_U10") (pintype "power_in"))
      (node (ref "IC6") (pin "U11") (pinfunction "GND_U11") (pintype "power_in"))
      (node (ref "IC6") (pin "U12") (pinfunction "GND_U12") (pintype "power_in"))
      (node (ref "IC6") (pin "U13") (pinfunction "GND_U13") (pintype "power_in"))
      (node (ref "IC6") (pin "U14") (pinfunction "GND_U14") (pintype "power_in"))
      (node (ref "IC6") (pin "U15") (pinfunction "GND_U15") (pintype "power_in"))
      (node (ref "IC6") (pin "U16") (pinfunction "GND_U16") (pintype "power_in"))
      (node (ref "IC6") (pin "U17") (pinfunction "GND_U17") (pintype "power_in"))
      (node (ref "IC6") (pin "U18") (pinfunction "GND_U18") (pintype "power_in"))
      (node (ref "IC6") (pin "U9") (pinfunction "GND_U9") (pintype "power_in"))
      (node (ref "IC6") (pin "V12") (pinfunction "GND_V12") (pintype "power_in"))
      (node (ref "IC6") (pin "V13") (pinfunction "GND_V13") (pintype "power_in"))
      (node (ref "IC6") (pin "V14") (pinfunction "GND_V14") (pintype "power_in"))
      (node (ref "IC6") (pin "V15") (pinfunction "GND_V15") (pintype "power_in"))
      (node (ref "IC6") (pin "V16") (pinfunction "GND_V16") (pintype "power_in"))
      (node (ref "IC6") (pin "V17") (pinfunction "GND_V17") (pintype "power_in"))
      (node (ref "IC6") (pin "V2") (pinfunction "GND_V2") (pintype "power_in"))
      (node (ref "IC6") (pin "V22") (pinfunction "GND_V22") (pintype "power_in"))
      (node (ref "IC6") (pin "V25") (pinfunction "GND_V25") (pintype "power_in"))
      (node (ref "IC6") (pin "V5") (pinfunction "GND_V5") (pintype "power_in"))
      (node (ref "IC6") (pin "V9") (pinfunction "GND_V9") (pintype "power_in"))
      (node (ref "IC6") (pin "W10") (pinfunction "GND_W10") (pintype "power_in"))
      (node (ref "IC6") (pin "W11") (pinfunction "GND_W11") (pintype "power_in"))
      (node (ref "IC6") (pin "W12") (pinfunction "GND_W12") (pintype "power_in"))
      (node (ref "IC6") (pin "W13") (pinfunction "GND_W13") (pintype "power_in"))
      (node (ref "IC6") (pin "W14") (pinfunction "GND_W14") (pintype "power_in"))
      (node (ref "IC6") (pin "W15") (pinfunction "GND_W15") (pintype "power_in"))
      (node (ref "IC6") (pin "W16") (pinfunction "GND_W16") (pintype "power_in"))
      (node (ref "IC6") (pin "W17") (pinfunction "GND_W17") (pintype "power_in"))
      (node (ref "IC6") (pin "W18") (pinfunction "GND_W18") (pintype "power_in"))
      (node (ref "IC6") (pin "W9") (pinfunction "GND_W9") (pintype "power_in"))
    )
    (net (code "2") (name "P1V1") (class "Default")
      (node (ref "C104") (pin "2") (pinfunction "2_2") (pintype "passive"))
      (node (ref "C105") (pin "2") (pinfunction "2_2") (pintype "passive"))
      (node (ref "C106") (pin "1") (pinfunction "1_1") (pintype "passive"))
      (node (ref "C110") (pin "2") (pinfunction "2_2") (pintype "passive"))
      (node (ref "C111") (pin "2") (pinfunction "2_2") (pintype "passive"))
      (node (ref "C112") (pin "2") (pinfunction "2_2") (pintype "passive"))
      (node (ref "C113") (pin "2") (pinfunction "2_2") (pintype "passive"))
      (node (ref "C114") (pin "2") (pinfunction "2_2") (pintype "passive"))
      (node (ref "C115") (pin "2") (pinfunction "2_2") (pintype "passive"))
      (node (ref "C116") (pin "2") (pinfunction "2_2") (pintype "passive"))
      (node (ref "C117") (pin "2") (pinfunction "2_2") (pintype "passive"))
      (node (ref "C118") (pin "2") (pinfunction "2_2") (pintype "passive"))
      (node (ref "C119") (pin "2") (pinfunction "2_2") (pintype "passive"))
      (node (ref "C120") (pin "2") (pinfunction "2_2") (pintype "passive"))
      (node (ref "C121") (pin "2") (pinfunction "2_2") (pintype "passive"))
      (node (ref "C122") (pin "2") (pinfunction "2_2") (pintype "passive"))
      (node (ref "C123") (pin "2") (pinfunction "2_2") (pintype "passive"))
      (node (ref "C124") (pin "2") (pinfunction "2_2") (pintype "passive"))
      (node (ref "C125") (pin "2") (pinfunction "2_2") (pintype "passive"))
      (node (ref "C126") (pin "2") (pinfunction "2_2") (pintype "passive"))
      (node (ref "C127") (pin "2") (pinfunction "2_2") (pintype "passive"))
      (node (ref "IC6") (pin "K11") (pinfunction "VCC_K11") (pintype "power_in"))
      (node (ref "IC6") (pin "K12") (pinfunction "VCC_K12") (pintype "power_in"))
      (node (ref "IC6") (pin "K13") (pinfunction "VCC_K13") (pintype "power_in"))
      (node (ref "IC6") (pin "K14") (pinfunction "VCC_K14") (pintype "power_in"))
      (node (ref "IC6") (pin "K15") (pinfunction "VCC_K15") (pintype "power_in"))
      (node (ref "IC6") (pin "K16") (pinfunction "VCC_K16") (pintype "power_in"))
      (node (ref "IC6") (pin "L10") (pinfunction "VCC_L10") (pintype "power_in"))
      (node (ref "IC6") (pin "L17") (pinfunction "VCC_L17") (pintype "power_in"))
      (node (ref "IC6") (pin "M10") (pinfunction "VCC_M10") (pintype "power_in"))
      (node (ref "IC6") (pin "M17") (pinfunction "VCC_M17") (pintype "power_in"))
      (node (ref "IC6") (pin "N10") (pinfunction "VCC_N10") (pintype "power_in"))
      (node (ref "IC6") (pin "N17") (pinfunction "VCC_N17") (pintype "power_in"))
      (node (ref "IC6") (pin "P10") (pinfunction "VCC_P10") (pintype "power_in"))
      (node (ref "IC6") (pin "P17") (pinfunction "VCC_P17") (pintype "power_in"))
      (node (ref "IC6") (pin "R10") (pinfunction "VCC_R10") (pintype "power_in"))
      (node (ref "IC6") (pin "R17") (pinfunction "VCC_R17") (pintype "power_in"))
      (node (ref "IC6") (pin "T10") (pinfunction "VCC_T10") (pintype "power_in"))
      (node (ref "IC6") (pin "T11") (pinfunction "VCC_T11") (pintype "power_in"))
      (node (ref "IC6") (pin "T12") (pinfunction "VCC_T12") (pintype "power_in"))
      (node (ref "IC6") (pin "T13") (pinfunction "VCC_T13") (pintype "power_in"))
      (node (ref "IC6") (pin "T14") (pinfunction "VCC_T14") (pintype "power_in"))
      (node (ref "IC6") (pin "T15") (pinfunction "VCC_T15") (pintype "power_in"))
      (node (ref "IC6") (pin "T16") (pinfunction "VCC_T16") (pintype "power_in"))
      (node (ref "IC6") (pin "T17") (pinfunction "VCC_T17") (pintype "power_in"))
    )
    (net (code "3") (name "P2V5") (class "Default")
      (node (ref "C100") (pin "2") (pinfunction "2_2") (pintype "passive"))
      (node (ref "C101") (pin "1") (pinfunction "1_1") (pintype "passive"))
      (node (ref "C54") (pin "2") (pinfunction "2_2") (pintype "passive"))
      (node (ref "C58") (pin "2") (pinfunction "2_2") (pintype "passive"))
      (node (ref "C59") (pin "2") (pinfunction "2_2") (pintype "passive"))
      (node (ref "C60") (pin "2") (pinfunction "2_2") (pintype "passive"))
      (node (ref "C61") (pin "2") (pinfunction "2_2") (pintype "passive"))
      (node (ref "C62") (pin "2") (pinfunction "2_2") (pintype "passive"))
      (node (ref "C63") (pin "2") (pinfunction "2_2") (pintype "passive"))
      (node (ref "C64") (pin "2") (pinfunction "2_2") (pintype "passive"))
      (node (ref "C65") (pin "2") (pinfunction "2_2") (pintype "passive"))
      (node (ref "C66") (pin "2") (pinfunction "2_2") (pintype "passive"))
      (node (ref "C68") (pin "2") (pinfunction "2_2") (pintype "passive"))
      (node (ref "C69") (pin "2") (pinfunction "2_2") (pintype "passive"))
      (node (ref "C76") (pin "2") (pinfunction "2_2") (pintype "passive"))
      (node (ref "C77") (pin "2") (pinfunction "2_2") (pintype "passive"))
      (node (ref "C90") (pin "2") (pinfunction "2_2") (pintype "passive"))
      (node (ref "C92") (pin "2") (pinfunction "2_2") (pintype "passive"))
      (node (ref "C93") (pin "2") (pinfunction "2_2") (pintype "passive"))
      (node (ref "C94") (pin "2") (pinfunction "2_2") (pintype "passive"))
      (node (ref "C95") (pin "2") (pinfunction "2_2") (pintype "passive"))
      (node (ref "C96") (pin "2") (pinfunction "2_2") (pintype "passive"))
      (node (ref "C97") (pin "2") (pinfunction "2_2") (pintype "passive"))
      (node (ref "C98") (pin "2") (pinfunction "2_2") (pintype "passive"))
      (node (ref "C99") (pin "2") (pinfunction "2_2") (pintype "passive"))
      (node (ref "IC6") (pin "H11") (pinfunction "VCCAUX_H11") (pintype "power_in"))
      (node (ref "IC6") (pin "H14") (pinfunction "VCCAUX_H14") (pintype "power_in"))
      (node (ref "IC6") (pin "H17") (pinfunction "VCCAUX_H17") (pintype "power_in"))
      (node (ref "IC6") (pin "J19") (pinfunction "VCCIO2_J19") (pintype "power_in"))
      (node (ref "IC6") (pin "K19") (pinfunction "VCCAUX_K19") (pintype "power_in"))
      (node (ref "IC6") (pin "K8") (pinfunction "VCCIO7_K8") (pintype "power_in"))
      (node (ref "IC6") (pin "L19") (pinfunction "VCCIO2_L19") (pintype "power_in"))
      (node (ref "IC6") (pin "L8") (pinfunction "VCCAUX_L8") (pintype "power_in"))
      (node (ref "IC6") (pin "M19") (pinfunction "VCCIO2_M19") (pintype "power_in"))
      (node (ref "IC6") (pin "M8") (pinfunction "VCCIO7_M8") (pintype "power_in"))
      (node (ref "IC6") (pin "N19") (pinfunction "VCCIO2_N19") (pintype "power_in"))
      (node (ref "IC6") (pin "N8") (pinfunction "VCCIO7_N8") (pintype "power_in"))
      (node (ref "IC6") (pin "P19") (pinfunction "VCCIO3_P19") (pintype "power_in"))
      (node (ref "IC6") (pin "P8") (pinfunction "VCCIO6_P8") (pintype "power_in"))
      (node (ref "IC6") (pin "R19") (pinfunction "VCCIO3_R19") (pintype "power_in"))
      (node (ref "IC6") (pin "R8") (pinfunction "VCCIO6_R8") (pintype "power_in"))
      (node (ref "IC6") (pin "T19") (pinfunction "VCCAUX_T19") (pintype "power_in"))
      (node (ref "IC6") (pin "T8") (pinfunction "VCCAUX_T8") (pintype "power_in"))
      (node (ref "IC6") (pin "U19") (pinfunction "VCCIO3_U19") (pintype "power_in"))
      (node (ref "IC6") (pin "U8") (pinfunction "VCCIO6_U8") (pintype "power_in"))
      (node (ref "IC6") (pin "V8") (pinfunction "VCCIO6_V8") (pintype "power_in"))
      (node (ref "IC6") (pin "W19") (pinfunction "VCCAUX_W19") (pintype "power_in"))
      (node (ref "IC6") (pin "W8") (pinfunction "VCCAUX_W8") (pintype "power_in"))
    )
    (net (code "4") (name "P3V3") (class "Default")
      (node (ref "C47") (pin "2") (pinfunction "2_2") (pintype "passive"))
      (node (ref "C48") (pin "2") (pinfunction "2_2") (pintype "passive"))
      (node (ref "C49") (pin "2") (pinfunction "2_2") (pintype "passive"))
      (node (ref "C50") (pin "2") (pinfunction "2_2") (pintype "passive"))
      (node (ref "C51") (pin "2") (pinfunction "2_2") (pintype "passive"))
      (node (ref "C53") (pin "2") (pinfunction "2_2") (pintype "passive"))
      (node (ref "C55") (pin "2") (pinfunction "2_2") (pintype "passive"))
      (node (ref "C56") (pin "2") (pinfunction "2_2") (pintype "passive"))
      (node (ref "C75") (pin "2") (pinfunction "2_2") (pintype "passive"))
      (node (ref "C86") (pin "2") (pinfunction "2_2") (pintype "passive"))
      (node (ref "C89") (pin "1") (pinfunction "1_1") (pintype "passive"))
      (node (ref "IC6") (pin "H10") (pinfunction "VCCIO0_H10") (pintype "power_in"))
      (node (ref "IC6") (pin "H12") (pinfunction "VCCIO0_H12") (pintype "power_in"))
      (node (ref "IC6") (pin "H13") (pinfunction "VCCIO0_H13") (pintype "power_in"))
      (node (ref "IC6") (pin "H15") (pinfunction "VCCIO1_H15") (pintype "power_in"))
      (node (ref "IC6") (pin "H16") (pinfunction "VCCIO1_H16") (pintype "power_in"))
      (node (ref "IC6") (pin "H18") (pinfunction "VCCIO1_H18") (pintype "power_in"))
      (node (ref "IC6") (pin "V10") (pinfunction "VCCIO8_V10") (pintype "power_in"))
      (node (ref "IC6") (pin "V11") (pinfunction "VCCIO8_V11") (pintype "power_in"))
      (node (ref "IC6") (pin "V18") (pinfunction "VCCIO4_V18") (pintype "power_in"))
      (node (ref "IC6") (pin "V19") (pinfunction "VCCIO4_V19") (pintype "power_in"))
    )
    (net (code "5") (name "unconnected-(IC6J-RESERVED-PadAD7)") (class "Default")
      (node (ref "IC6") (pin "AD7") (pinfunction "RESERVED_AD7") (pintype "passive+no_connect"))
    )
    (net (code "6") (name "unconnected-(IC6J-RESERVED-PadAD8)") (class "Default")
      (node (ref "IC6") (pin "AD8") (pinfunction "RESERVED_AD8") (pintype "passive+no_connect"))
    )
    (net (code "7") (name "unconnected-(IC6J-RESERVED-PadAD10)") (class "Default")
      (node (ref "IC6") (pin "AD10") (pinfunction "RESERVED_AD10") (pintype "passive+no_connect"))
    )
    (net (code "8") (name "unconnected-(IC6J-RESERVED-PadAD11)") (class "Default")
      (node (ref "IC6") (pin "AD11") (pinfunction "RESERVED_AD11") (pintype "passive+no_connect"))
    )
    (net (code "9") (name "unconnected-(IC6J-RESERVED-PadAD13)") (class "Default")
      (node (ref "IC6") (pin "AD13") (pinfunction "RESERVED_AD13") (pintype "passive+no_connect"))
    )
    (net (code "10") (name "unconnected-(IC6J-RESERVED-PadAD14)") (class "Default")
      (node (ref "IC6") (pin "AD14") (pinfunction "RESERVED_AD14") (pintype "passive+no_connect"))
    )
    (net (code "11") (name "unconnected-(IC6J-RESERVED-PadAD16)") (class "Default")
      (node (ref "IC6") (pin "AD16") (pinfunction "RESERVED_AD16") (pintype "passive+no_connect"))
    )
    (net (code "12") (name "unconnected-(IC6J-RESERVED-PadAD17)") (class "Default")
      (node (ref "IC6") (pin "AD17") (pinfunction "RESERVED_AD17") (pintype "passive+no_connect"))
    )
    (net (code "13") (name "unconnected-(IC6J-RESERVED-PadAD19)") (class "Default")
      (node (ref "IC6") (pin "AD19") (pinfunction "RESERVED_AD19") (pintype "passive+no_connect"))
    )
    (net (code "14") (name "unconnected-(IC6J-RESERVED-PadAD20)") (class "Default")
      (node (ref "IC6") (pin "AD20") (pinfunction "RESERVED_AD20") (pintype "passive+no_connect"))
    )
    (net (code "15") (name "unconnected-(IC6J-RESERVED-PadAD22)") (class "Default")
      (node (ref "IC6") (pin "AD22") (pinfunction "RESERVED_AD22") (pintype "passive+no_connect"))
    )
    (net (code "16") (name "unconnected-(IC6J-RESERVED-PadAD23)") (class "Default")
      (node (ref "IC6") (pin "AD23") (pinfunction "RESERVED_AD23") (pintype "passive+no_connect"))
    )
    (net (code "17") (name "unconnected-(IC6M-NC-PadAA3)") (class "Default")
      (node (ref "IC6") (pin "AA3") (pinfunction "NC_AA3") (pintype "passive+no_connect"))
    )
    (net (code "18") (name "unconnected-(IC6M-NC-PadAA4)") (class "Default")
      (node (ref "IC6") (pin "AA4") (pinfunction "NC_AA4") (pintype "passive+no_connect"))
    )
    (net (code "19") (name "unconnected-(IC6M-NC-PadAA5)") (class "Default")
      (node (ref "IC6") (pin "AA5") (pinfunction "NC_AA5") (pintype "passive+no_connect"))
    )
    (net (code "20") (name "unconnected-(IC6M-NC-PadC12)") (class "Default")
      (node (ref "IC6") (pin "C12") (pinfunction "NC_C12") (pintype "passive+no_connect"))
    )
    (net (code "21") (name "unconnected-(IC6M-NC-PadC15)") (class "Default")
      (node (ref "IC6") (pin "C15") (pinfunction "NC_C15") (pintype "passive+no_connect"))
    )
    (net (code "22") (name "unconnected-(IC6M-NC-PadD12)") (class "Default")
      (node (ref "IC6") (pin "D12") (pinfunction "NC_D12") (pintype "passive+no_connect"))
    )
    (net (code "23") (name "unconnected-(IC6M-NC-PadD15)") (class "Default")
      (node (ref "IC6") (pin "D15") (pinfunction "NC_D15") (pintype "passive+no_connect"))
    )
    (net (code "24") (name "unconnected-(IC6M-NC-PadF8)") (class "Default")
      (node (ref "IC6") (pin "F8") (pinfunction "NC_F8") (pintype "passive+no_connect"))
    )
    (net (code "25") (name "unconnected-(IC6M-NC-PadF9)") (class "Default")
      (node (ref "IC6") (pin "F9") (pinfunction "NC_F9") (pintype "passive+no_connect"))
    )
    (net (code "26") (name "unconnected-(IC6M-NC-PadF10)") (class "Default")
      (node (ref "IC6") (pin "F10") (pinfunction "NC_F10") (pintype "passive+no_connect"))
    )
    (net (code "27") (name "unconnected-(IC6M-NC-PadF12)") (class "Default")
      (node (ref "IC6") (pin "F12") (pinfunction "NC_F12") (pintype "passive+no_connect"))
    )
    (net (code "28") (name "unconnected-(IC6M-NC-PadF13)") (class "Default")
      (node (ref "IC6") (pin "F13") (pinfunction "NC_F13") (pintype "passive+no_connect"))
    )
    (net (code "29") (name "unconnected-(IC6M-NC-PadF14)") (class "Default")
      (node (ref "IC6") (pin "F14") (pinfunction "NC_F14") (pintype "passive+no_connect"))
    )
    (net (code "30") (name "unconnected-(IC6M-NC-PadF15)") (class "Default")
      (node (ref "IC6") (pin "F15") (pinfunction "NC_F15") (pintype "passive+no_connect"))
    )
    (net (code "31") (name "unconnected-(IC6M-NC-PadF17)") (class "Default")
      (node (ref "IC6") (pin "F17") (pinfunction "NC_F17") (pintype "passive+no_connect"))
    )
    (net (code "32") (name "unconnected-(IC6M-NC-PadF18)") (class "Default")
      (node (ref "IC6") (pin "F18") (pinfunction "NC_F18") (pintype "passive+no_connect"))
    )
    (net (code "33") (name "unconnected-(IC6M-NC-PadF19)") (class "Default")
      (node (ref "IC6") (pin "F19") (pinfunction "NC_F19") (pintype "passive+no_connect"))
    )
  )
)
